# BOSS_FA-1.net
KiCad netlist of a schematic drawn in EAGLE
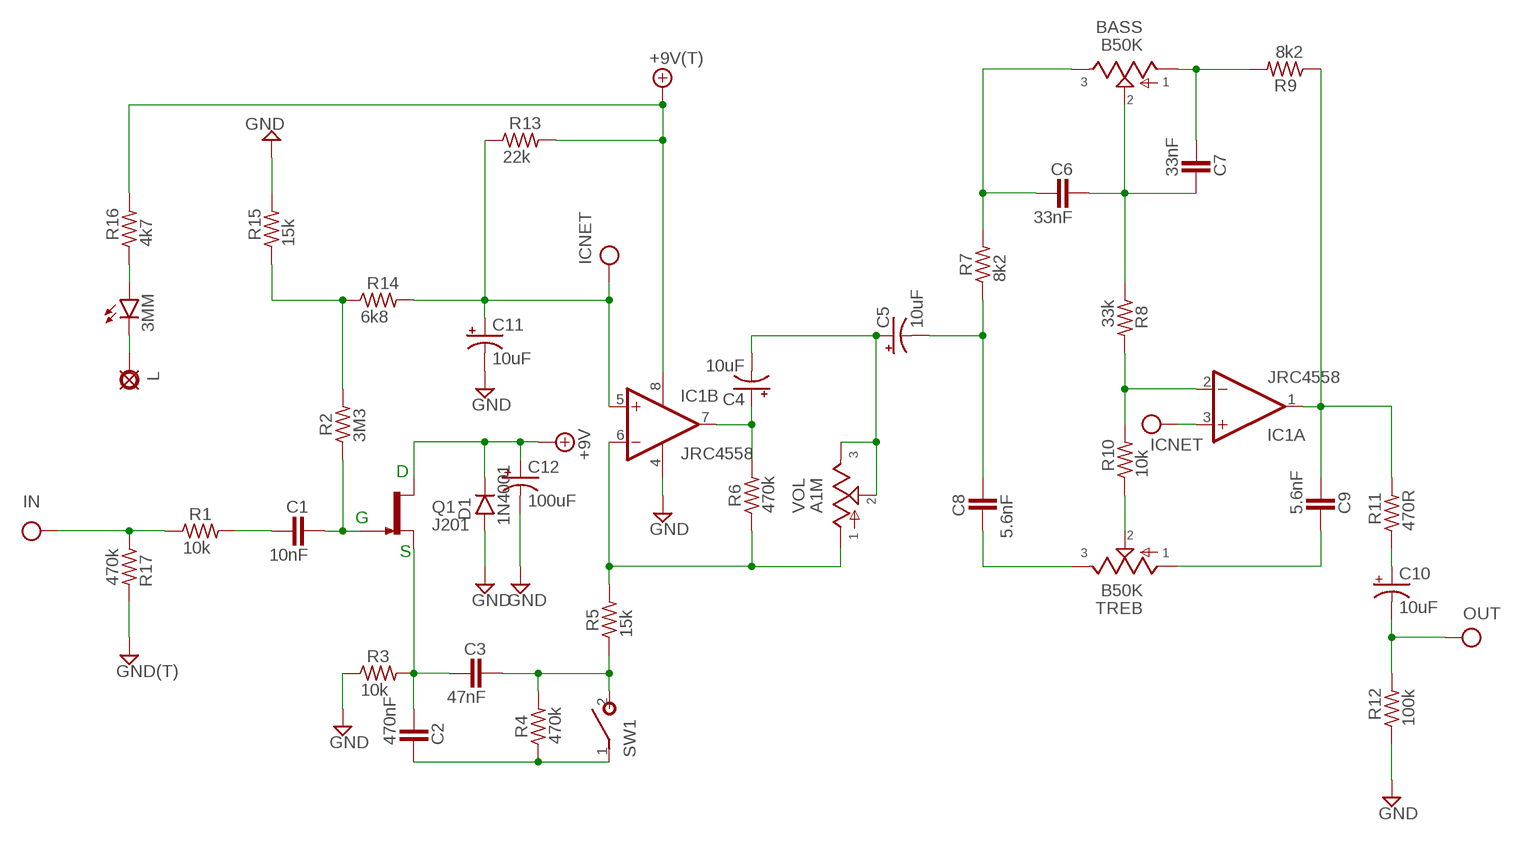
[diagram p0: schematic, sheet 1]

(export (version "E")
  (design (tool "Eeschema 10.0.6"))
  (components
    (comp (ref "+9V")
      (value "+9V(T)")
      (footprint "eagle-import:SQUARE")
      (libsource (lib "eagle-import") (part "+9V(T)"))
    )
    (comp (ref "3MM")
      (value "LED3MM")
      (footprint "eagle-import:LED3MM")
      (libsource (lib "eagle-import") (part "LED3MM"))
    )
    (comp (ref "BASS")
      (value "B50K")
      (footprint "eagle-import:16MM_PCB_PADS")
      (libsource (lib "eagle-import") (part "POT16MM_PCB_PADS"))
    )
    (comp (ref "C1")
      (value "10nF")
      (footprint "eagle-import:072X025")
      (libsource (lib "eagle-import") (part "072X0252"))
    )
    (comp (ref "C2")
      (value "470nF")
      (footprint "eagle-import:072X035")
      (libsource (lib "eagle-import") (part "072X0352"))
    )
    (comp (ref "C3")
      (value "47nF")
      (footprint "eagle-import:072X025")
      (libsource (lib "eagle-import") (part "072X0252"))
    )
    (comp (ref "C4")
      (value "10uF")
      (footprint "eagle-import:050_020_1")
      (libsource (lib "eagle-import") (part "0501"))
    )
    (comp (ref "C5")
      (value "10uF")
      (footprint "eagle-import:050_020_1")
      (libsource (lib "eagle-import") (part "0501"))
    )
    (comp (ref "C6")
      (value "33nF")
      (footprint "eagle-import:072X025")
      (libsource (lib "eagle-import") (part "072X0252"))
    )
    (comp (ref "C7")
      (value "33nF")
      (footprint "eagle-import:072X025")
      (libsource (lib "eagle-import") (part "072X0252"))
    )
    (comp (ref "C8")
      (value "5.6nF")
      (footprint "eagle-import:072X025")
      (libsource (lib "eagle-import") (part "072X0252"))
    )
    (comp (ref "C9")
      (value "5.6nF")
      (footprint "eagle-import:072X025")
      (libsource (lib "eagle-import") (part "072X0252"))
    )
    (comp (ref "C10")
      (value "10uF")
      (footprint "eagle-import:050_020_1")
      (libsource (lib "eagle-import") (part "0501"))
    )
    (comp (ref "C11")
      (value "10uF")
      (footprint "eagle-import:050_020_1")
      (libsource (lib "eagle-import") (part "0501"))
    )
    (comp (ref "C12")
      (value "100uF")
      (footprint "eagle-import:063_025")
      (libsource (lib "eagle-import") (part "0631"))
    )
    (comp (ref "D1")
      (value "1N4001")
      (footprint "eagle-import:DO41-3")
      (libsource (lib "eagle-import") (part "1N400X.3"))
    )
    (comp (ref "G")
      (value "GND(T)")
      (footprint "eagle-import:SQUARE")
      (libsource (lib "eagle-import") (part "GND(T)"))
    )
    (comp (ref "IC1")
      (value "JRC4558")
      (footprint "eagle-import:DIL08")
      (libsource (lib "eagle-import") (part "4558NLM"))
    )
    (comp (ref "IN")
      (value "IN(T)")
      (footprint "eagle-import:SQUARE")
      (libsource (lib "eagle-import") (part "IN(T)"))
    )
    (comp (ref "L")
      (value "PAD")
      (footprint "eagle-import:SQUARE")
      (libsource (lib "eagle-import") (part "PAD"))
    )
    (comp (ref "OUT")
      (value "OUT(T)")
      (footprint "eagle-import:SQUARE")
      (libsource (lib "eagle-import") (part "OUT(T)"))
    )
    (comp (ref "Q1")
      (value "J201")
      (footprint "eagle-import:TO92-")
      (libsource (lib "eagle-import") (part "J201"))
    )
    (comp (ref "R1")
      (value "10k")
      (footprint "eagle-import:R0207_3")
      (libsource (lib "eagle-import") (part "6MM.3"))
    )
    (comp (ref "R2")
      (value "3M3")
      (footprint "eagle-import:R0207_3")
      (libsource (lib "eagle-import") (part "6MM.3"))
    )
    (comp (ref "R3")
      (value "10k")
      (footprint "eagle-import:R0207_3")
      (libsource (lib "eagle-import") (part "6MM.3"))
    )
    (comp (ref "R4")
      (value "470k")
      (footprint "eagle-import:R0207_3")
      (libsource (lib "eagle-import") (part "6MM.3"))
    )
    (comp (ref "R5")
      (value "15k")
      (footprint "eagle-import:R0207_3")
      (libsource (lib "eagle-import") (part "6MM.3"))
    )
    (comp (ref "R6")
      (value "470k")
      (footprint "eagle-import:R0207_3")
      (libsource (lib "eagle-import") (part "6MM.3"))
    )
    (comp (ref "R7")
      (value "8k2")
      (footprint "eagle-import:R0207_3")
      (libsource (lib "eagle-import") (part "6MM.3"))
    )
    (comp (ref "R8")
      (value "33k")
      (footprint "eagle-import:R0207_3")
      (libsource (lib "eagle-import") (part "6MM.3"))
    )
    (comp (ref "R9")
      (value "8k2")
      (footprint "eagle-import:R0207_3")
      (libsource (lib "eagle-import") (part "6MM.3"))
    )
    (comp (ref "R10")
      (value "10k")
      (footprint "eagle-import:R0207_3")
      (libsource (lib "eagle-import") (part "6MM.3"))
    )
    (comp (ref "R11")
      (value "470R")
      (footprint "eagle-import:R0207_3")
      (libsource (lib "eagle-import") (part "6MM.3"))
    )
    (comp (ref "R12")
      (value "100k")
      (footprint "eagle-import:R0207_3")
      (libsource (lib "eagle-import") (part "6MM.3"))
    )
    (comp (ref "R13")
      (value "22k")
      (footprint "eagle-import:R0207_3")
      (libsource (lib "eagle-import") (part "6MM.3"))
    )
    (comp (ref "R14")
      (value "6k8")
      (footprint "eagle-import:R0207_3")
      (libsource (lib "eagle-import") (part "6MM.3"))
    )
    (comp (ref "R15")
      (value "15k")
      (footprint "eagle-import:R0207_3")
      (libsource (lib "eagle-import") (part "6MM.3"))
    )
    (comp (ref "R16")
      (value "4k7")
      (footprint "eagle-import:R0207_3")
      (libsource (lib "eagle-import") (part "6MM.3"))
    )
    (comp (ref "R17")
      (value "470k")
      (footprint "eagle-import:R0207_3")
      (libsource (lib "eagle-import") (part "6MM.3"))
    )
    (comp (ref "SW1")
      (value "SPST")
      (footprint "eagle-import:SPST")
      (libsource (lib "eagle-import") (part "SPST"))
    )
    (comp (ref "TREB")
      (value "B50K")
      (footprint "eagle-import:16MM_PCB_PADS")
      (libsource (lib "eagle-import") (part "POT16MM_PCB_PADS"))
    )
    (comp (ref "VOL")
      (value "A1M")
      (footprint "eagle-import:16MM_PCB_PADS")
      (libsource (lib "eagle-import") (part "POT16MM_PCB_PADS"))
    )
  )
  (nets
    (net (code "1") (name "+9V") (class "Default")
      (node (ref "+9V") (pin "1") (pinfunction "+9V_1") (pintype "power_in"))
      (node (ref "C12") (pin "+") (pinfunction "+_+") (pintype "passive"))
      (node (ref "D1") (pin "C") (pinfunction "C_C") (pintype "passive"))
      (node (ref "IC1") (pin "8") (pinfunction "V+_8") (pintype "power_in"))
      (node (ref "Q1") (pin "3") (pinfunction "D_3") (pintype "passive"))
      (node (ref "R13") (pin "2") (pinfunction "2_2") (pintype "passive"))
      (node (ref "R16") (pin "2") (pinfunction "2_2") (pintype "passive"))
    )
    (net (code "2") (name "GND") (class "Default")
      (node (ref "C11") (pin "-") (pinfunction "-_-") (pintype "passive"))
      (node (ref "C12") (pin "-") (pinfunction "-_-") (pintype "passive"))
      (node (ref "D1") (pin "A") (pinfunction "A_A") (pintype "passive"))
      (node (ref "G") (pin "1") (pinfunction "GND_1") (pintype "power_in"))
      (node (ref "IC1") (pin "4") (pinfunction "V-_4") (pintype "power_in"))
      (node (ref "R12") (pin "1") (pinfunction "1_1") (pintype "passive"))
      (node (ref "R15") (pin "2") (pinfunction "2_2") (pintype "passive"))
      (node (ref "R17") (pin "2") (pinfunction "2_2") (pintype "passive"))
      (node (ref "R3") (pin "1") (pinfunction "1_1") (pintype "passive"))
    )
    (net (code "3") (name "ICNET") (class "Default")
      (node (ref "C11") (pin "+") (pinfunction "+_+") (pintype "passive"))
      (node (ref "IC1") (pin "3") (pinfunction "+IN_3") (pintype "input"))
      (node (ref "IC1") (pin "5") (pinfunction "+IN_5") (pintype "input"))
      (node (ref "R13") (pin "1") (pinfunction "1_1") (pintype "passive"))
      (node (ref "R14") (pin "2") (pinfunction "2_2") (pintype "passive"))
    )
    (net (code "4") (name "IN(T)") (class "Default")
      (node (ref "IN") (pin "1") (pinfunction "IN_1") (pintype "power_in"))
      (node (ref "R1") (pin "1") (pinfunction "1_1") (pintype "passive"))
      (node (ref "R17") (pin "1") (pinfunction "1_1") (pintype "passive"))
    )
    (net (code "5") (name "Net-(3MM-C)") (class "Default")
      (node (ref "3MM") (pin "K") (pinfunction "C_K") (pintype "passive"))
      (node (ref "L") (pin "1") (pinfunction "PAD_1") (pintype "passive"))
    )
    (net (code "6") (name "Net-(3MM-PadA)") (class "Default")
      (node (ref "3MM") (pin "A") (pinfunction "A_A") (pintype "passive"))
      (node (ref "R16") (pin "1") (pinfunction "1_1") (pintype "passive"))
    )
    (net (code "7") (name "Net-(BASS-Pad1)") (class "Default")
      (node (ref "BASS") (pin "1") (pinfunction "1_1") (pintype "passive"))
      (node (ref "C7") (pin "1") (pinfunction "1_1") (pintype "passive"))
      (node (ref "R9") (pin "2") (pinfunction "2_2") (pintype "passive"))
    )
    (net (code "8") (name "Net-(BASS-Pad2)") (class "Default")
      (node (ref "BASS") (pin "2") (pinfunction "2_2") (pintype "passive"))
      (node (ref "C6") (pin "2") (pinfunction "2_2") (pintype "passive"))
      (node (ref "C7") (pin "2") (pinfunction "2_2") (pintype "passive"))
      (node (ref "R8") (pin "1") (pinfunction "1_1") (pintype "passive"))
    )
    (net (code "9") (name "Net-(BASS-Pad3)") (class "Default")
      (node (ref "BASS") (pin "3") (pinfunction "3_3") (pintype "passive"))
      (node (ref "C6") (pin "1") (pinfunction "1_1") (pintype "passive"))
      (node (ref "R7") (pin "2") (pinfunction "2_2") (pintype "passive"))
    )
    (net (code "10") (name "Net-(C1-Pad1)") (class "Default")
      (node (ref "C1") (pin "1") (pinfunction "1_1") (pintype "passive"))
      (node (ref "R1") (pin "2") (pinfunction "2_2") (pintype "passive"))
    )
    (net (code "11") (name "Net-(C4-Pad-)") (class "Default")
      (node (ref "C4") (pin "-") (pinfunction "-_-") (pintype "passive"))
      (node (ref "C5") (pin "+") (pinfunction "+_+") (pintype "passive"))
      (node (ref "VOL") (pin "2") (pinfunction "2_2") (pintype "passive"))
      (node (ref "VOL") (pin "3") (pinfunction "3_3") (pintype "passive"))
    )
    (net (code "12") (name "Net-(C5-Pad-)") (class "Default")
      (node (ref "C5") (pin "-") (pinfunction "-_-") (pintype "passive"))
      (node (ref "C8") (pin "2") (pinfunction "2_2") (pintype "passive"))
      (node (ref "R7") (pin "1") (pinfunction "1_1") (pintype "passive"))
    )
    (net (code "13") (name "Net-(C8-Pad1)") (class "Default")
      (node (ref "C8") (pin "1") (pinfunction "1_1") (pintype "passive"))
      (node (ref "TREB") (pin "3") (pinfunction "3_3") (pintype "passive"))
    )
    (net (code "14") (name "Net-(C9-Pad2)") (class "Default")
      (node (ref "C9") (pin "2") (pinfunction "2_2") (pintype "passive"))
      (node (ref "TREB") (pin "1") (pinfunction "1_1") (pintype "passive"))
    )
    (net (code "15") (name "Net-(C10-Pad+)") (class "Default")
      (node (ref "C10") (pin "+") (pinfunction "+_+") (pintype "passive"))
      (node (ref "R11") (pin "1") (pinfunction "1_1") (pintype "passive"))
    )
    (net (code "16") (name "Net-(IC1A--IN)") (class "Default")
      (node (ref "IC1") (pin "2") (pinfunction "-IN_2") (pintype "input"))
      (node (ref "R10") (pin "2") (pinfunction "2_2") (pintype "passive"))
      (node (ref "R8") (pin "2") (pinfunction "2_2") (pintype "passive"))
    )
    (net (code "17") (name "Net-(IC1A-OUT)") (class "Default")
      (node (ref "C9") (pin "1") (pinfunction "1_1") (pintype "passive"))
      (node (ref "IC1") (pin "1") (pinfunction "OUT_1") (pintype "output"))
      (node (ref "R11") (pin "2") (pinfunction "2_2") (pintype "passive"))
      (node (ref "R9") (pin "1") (pinfunction "1_1") (pintype "passive"))
    )
    (net (code "18") (name "Net-(IC1B--IN)") (class "Default")
      (node (ref "IC1") (pin "6") (pinfunction "-IN_6") (pintype "input"))
      (node (ref "R5") (pin "2") (pinfunction "2_2") (pintype "passive"))
      (node (ref "R6") (pin "1") (pinfunction "1_1") (pintype "passive"))
      (node (ref "VOL") (pin "1") (pinfunction "1_1") (pintype "passive"))
    )
    (net (code "19") (name "Net-(IC1B-OUT)") (class "Default")
      (node (ref "C4") (pin "+") (pinfunction "+_+") (pintype "passive"))
      (node (ref "IC1") (pin "7") (pinfunction "OUT_7") (pintype "output"))
      (node (ref "R6") (pin "2") (pinfunction "2_2") (pintype "passive"))
    )
    (net (code "20") (name "Net-(Q1-G)") (class "Default")
      (node (ref "C1") (pin "2") (pinfunction "2_2") (pintype "passive"))
      (node (ref "Q1") (pin "1") (pinfunction "G_1") (pintype "passive"))
      (node (ref "R2") (pin "1") (pinfunction "1_1") (pintype "passive"))
    )
    (net (code "21") (name "Net-(Q1-S)") (class "Default")
      (node (ref "C2") (pin "1") (pinfunction "1_1") (pintype "passive"))
      (node (ref "C3") (pin "1") (pinfunction "1_1") (pintype "passive"))
      (node (ref "Q1") (pin "2") (pinfunction "S_2") (pintype "passive"))
      (node (ref "R3") (pin "2") (pinfunction "2_2") (pintype "passive"))
    )
    (net (code "22") (name "Net-(R10-Pad1)") (class "Default")
      (node (ref "R10") (pin "1") (pinfunction "1_1") (pintype "passive"))
      (node (ref "TREB") (pin "2") (pinfunction "2_2") (pintype "passive"))
    )
    (net (code "23") (name "Net-(R14-Pad1)") (class "Default")
      (node (ref "R14") (pin "1") (pinfunction "1_1") (pintype "passive"))
      (node (ref "R15") (pin "1") (pinfunction "1_1") (pintype "passive"))
      (node (ref "R2") (pin "2") (pinfunction "2_2") (pintype "passive"))
    )
    (net (code "24") (name "Net-(SW1-P)") (class "Default")
      (node (ref "C2") (pin "2") (pinfunction "2_2") (pintype "passive"))
      (node (ref "R4") (pin "1") (pinfunction "1_1") (pintype "passive"))
      (node (ref "SW1") (pin "1") (pinfunction "P_1") (pintype "passive"))
    )
    (net (code "25") (name "Net-(SW1-S)") (class "Default")
      (node (ref "C3") (pin "2") (pinfunction "2_2") (pintype "passive"))
      (node (ref "R4") (pin "2") (pinfunction "2_2") (pintype "passive"))
      (node (ref "R5") (pin "1") (pinfunction "1_1") (pintype "passive"))
      (node (ref "SW1") (pin "2") (pinfunction "S_2") (pintype "passive"))
    )
    (net (code "26") (name "OUT(T)") (class "Default")
      (node (ref "C10") (pin "-") (pinfunction "-_-") (pintype "passive"))
      (node (ref "OUT") (pin "1") (pinfunction "OUT_1") (pintype "power_in"))
      (node (ref "R12") (pin "2") (pinfunction "2_2") (pintype "passive"))
    )
  )
)
